# Schematic_Final.net
KiCad netlist of a schematic drawn in EAGLE
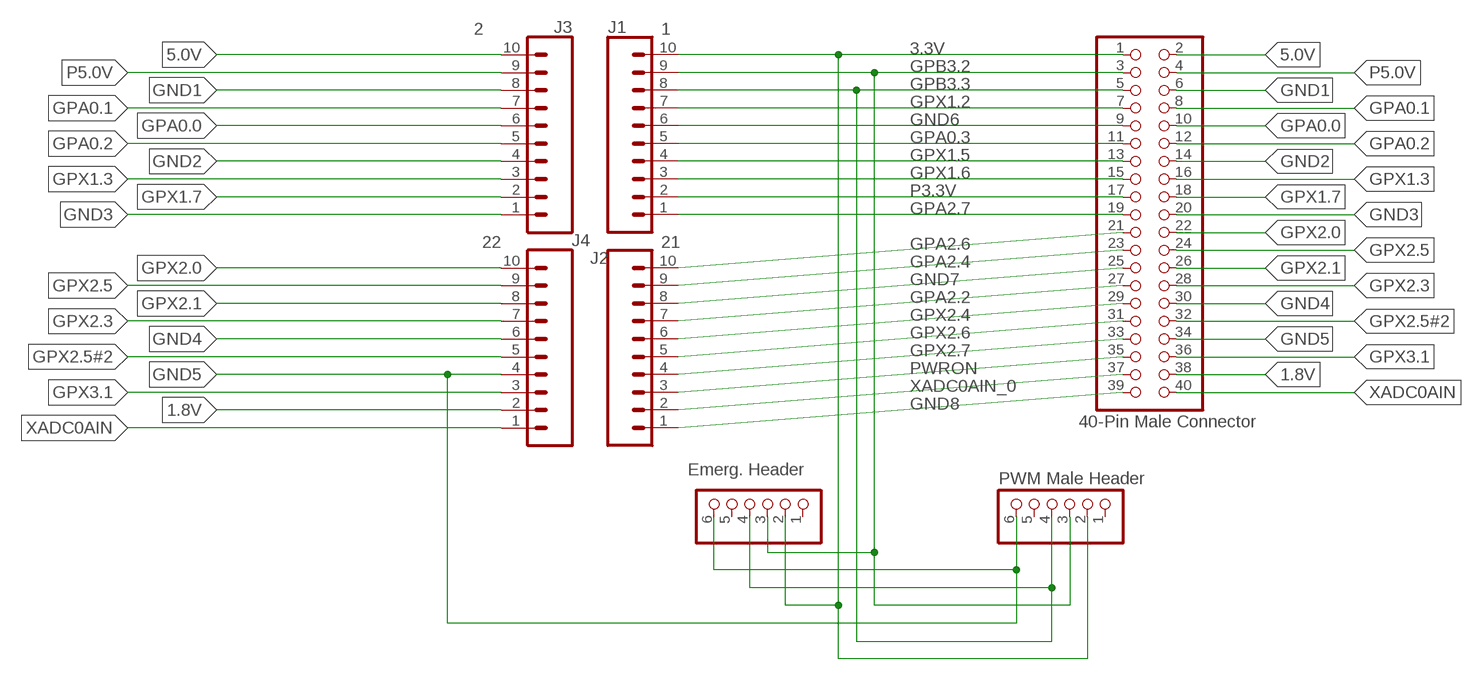
[diagram p0: schematic, sheet 1]

(export (version "E")
  (design (tool "Eeschema 10.0.6"))
  (components
    (comp (ref "J1")
      (value "1")
      (footprint "eagle-import:1X10")
      (libsource (lib "eagle-import") (part "CONN_10{dblquote}"))
    )
    (comp (ref "J2")
      (value "21")
      (footprint "eagle-import:1X10")
      (libsource (lib "eagle-import") (part "CONN_10{dblquote}"))
    )
    (comp (ref "J3")
      (value "2")
      (footprint "eagle-import:1X10")
      (libsource (lib "eagle-import") (part "CONN_10{dblquote}"))
    )
    (comp (ref "J4")
      (value "22")
      (footprint "eagle-import:1X10")
      (libsource (lib "eagle-import") (part "CONN_10{dblquote}"))
    )
    (comp (ref "JP1")
      (value "40-Pin Male Connector")
      (footprint "eagle-import:2X20")
      (libsource (lib "eagle-import") (part "PINHD-2X20"))
    )
    (comp (ref "JP2")
      (value "Emerg. Header")
      (footprint "eagle-import:1X06")
      (libsource (lib "eagle-import") (part "PINHD-1X6"))
    )
    (comp (ref "JP4")
      (value "PWM Male Header")
      (footprint "eagle-import:1X06")
      (libsource (lib "eagle-import") (part "PINHD-1X6"))
    )
  )
  (nets
    (net (code "1") (name "/3.3V") (class "Default")
      (node (ref "J1") (pin "10") (pinfunction "10_10") (pintype "passive"))
      (node (ref "JP1") (pin "1") (pinfunction "1_1") (pintype "passive"))
      (node (ref "JP2") (pin "2") (pinfunction "2_2") (pintype "passive"))
      (node (ref "JP4") (pin "2") (pinfunction "2_2") (pintype "passive"))
    )
    (net (code "2") (name "/GND6") (class "Default")
      (node (ref "J1") (pin "6") (pinfunction "6_6") (pintype "passive"))
      (node (ref "JP1") (pin "9") (pinfunction "9_9") (pintype "passive"))
    )
    (net (code "3") (name "/GND7") (class "Default")
      (node (ref "J2") (pin "8") (pinfunction "8_8") (pintype "passive"))
      (node (ref "JP1") (pin "25") (pinfunction "25_25") (pintype "passive"))
    )
    (net (code "4") (name "/GND8") (class "Default")
      (node (ref "J2") (pin "1") (pinfunction "1_1") (pintype "passive"))
      (node (ref "JP1") (pin "39") (pinfunction "39_39") (pintype "passive"))
    )
    (net (code "5") (name "/GPA0.3") (class "Default")
      (node (ref "J1") (pin "5") (pinfunction "5_5") (pintype "passive"))
      (node (ref "JP1") (pin "11") (pinfunction "11_11") (pintype "passive"))
    )
    (net (code "6") (name "/GPA2.2") (class "Default")
      (node (ref "J2") (pin "7") (pinfunction "7_7") (pintype "passive"))
      (node (ref "JP1") (pin "27") (pinfunction "27_27") (pintype "passive"))
    )
    (net (code "7") (name "/GPA2.4") (class "Default")
      (node (ref "J2") (pin "9") (pinfunction "9_9") (pintype "passive"))
      (node (ref "JP1") (pin "23") (pinfunction "23_23") (pintype "passive"))
    )
    (net (code "8") (name "/GPA2.6") (class "Default")
      (node (ref "J2") (pin "10") (pinfunction "10_10") (pintype "passive"))
      (node (ref "JP1") (pin "21") (pinfunction "21_21") (pintype "passive"))
    )
    (net (code "9") (name "/GPA2.7") (class "Default")
      (node (ref "J1") (pin "1") (pinfunction "1_1") (pintype "passive"))
      (node (ref "JP1") (pin "19") (pinfunction "19_19") (pintype "passive"))
    )
    (net (code "10") (name "/GPB3.2") (class "Default")
      (node (ref "J1") (pin "9") (pinfunction "9_9") (pintype "passive"))
      (node (ref "JP1") (pin "3") (pinfunction "3_3") (pintype "passive"))
      (node (ref "JP2") (pin "3") (pinfunction "3_3") (pintype "passive"))
      (node (ref "JP4") (pin "3") (pinfunction "3_3") (pintype "passive"))
    )
    (net (code "11") (name "/GPB3.3") (class "Default")
      (node (ref "J1") (pin "8") (pinfunction "8_8") (pintype "passive"))
      (node (ref "JP1") (pin "5") (pinfunction "5_5") (pintype "passive"))
      (node (ref "JP2") (pin "4") (pinfunction "4_4") (pintype "passive"))
      (node (ref "JP4") (pin "4") (pinfunction "4_4") (pintype "passive"))
    )
    (net (code "12") (name "/GPX1.2") (class "Default")
      (node (ref "J1") (pin "7") (pinfunction "7_7") (pintype "passive"))
      (node (ref "JP1") (pin "7") (pinfunction "7_7") (pintype "passive"))
    )
    (net (code "13") (name "/GPX1.5") (class "Default")
      (node (ref "J1") (pin "4") (pinfunction "4_4") (pintype "passive"))
      (node (ref "JP1") (pin "13") (pinfunction "13_13") (pintype "passive"))
    )
    (net (code "14") (name "/GPX1.6") (class "Default")
      (node (ref "J1") (pin "3") (pinfunction "3_3") (pintype "passive"))
      (node (ref "JP1") (pin "15") (pinfunction "15_15") (pintype "passive"))
    )
    (net (code "15") (name "/GPX2.4") (class "Default")
      (node (ref "J2") (pin "6") (pinfunction "6_6") (pintype "passive"))
      (node (ref "JP1") (pin "29") (pinfunction "29_29") (pintype "passive"))
    )
    (net (code "16") (name "/GPX2.6") (class "Default")
      (node (ref "J2") (pin "5") (pinfunction "5_5") (pintype "passive"))
      (node (ref "JP1") (pin "31") (pinfunction "31_31") (pintype "passive"))
    )
    (net (code "17") (name "/GPX2.7") (class "Default")
      (node (ref "J2") (pin "4") (pinfunction "4_4") (pintype "passive"))
      (node (ref "JP1") (pin "33") (pinfunction "33_33") (pintype "passive"))
    )
    (net (code "18") (name "/P3.3V") (class "Default")
      (node (ref "J1") (pin "2") (pinfunction "2_2") (pintype "passive"))
      (node (ref "JP1") (pin "17") (pinfunction "17_17") (pintype "passive"))
    )
    (net (code "19") (name "/PWRON") (class "Default")
      (node (ref "J2") (pin "3") (pinfunction "3_3") (pintype "passive"))
      (node (ref "JP1") (pin "35") (pinfunction "35_35") (pintype "passive"))
    )
    (net (code "20") (name "/XADC0AIN_0") (class "Default")
      (node (ref "J2") (pin "2") (pinfunction "2_2") (pintype "passive"))
      (node (ref "JP1") (pin "37") (pinfunction "37_37") (pintype "passive"))
    )
    (net (code "21") (name "1.8V") (class "Default")
      (node (ref "J4") (pin "2") (pinfunction "2_2") (pintype "passive"))
      (node (ref "JP1") (pin "38") (pinfunction "38_38") (pintype "passive"))
    )
    (net (code "22") (name "5.0V") (class "Default")
      (node (ref "J3") (pin "10") (pinfunction "10_10") (pintype "passive"))
      (node (ref "JP1") (pin "2") (pinfunction "2_2") (pintype "passive"))
    )
    (net (code "23") (name "GND1") (class "Default")
      (node (ref "J3") (pin "8") (pinfunction "8_8") (pintype "passive"))
      (node (ref "JP1") (pin "6") (pinfunction "6_6") (pintype "passive"))
    )
    (net (code "24") (name "GND2") (class "Default")
      (node (ref "J3") (pin "4") (pinfunction "4_4") (pintype "passive"))
      (node (ref "JP1") (pin "14") (pinfunction "14_14") (pintype "passive"))
    )
    (net (code "25") (name "GND3") (class "Default")
      (node (ref "J3") (pin "1") (pinfunction "1_1") (pintype "passive"))
      (node (ref "JP1") (pin "20") (pinfunction "20_20") (pintype "passive"))
    )
    (net (code "26") (name "GND4") (class "Default")
      (node (ref "J4") (pin "6") (pinfunction "6_6") (pintype "passive"))
      (node (ref "JP1") (pin "30") (pinfunction "30_30") (pintype "passive"))
    )
    (net (code "27") (name "GND5") (class "Default")
      (node (ref "J4") (pin "4") (pinfunction "4_4") (pintype "passive"))
      (node (ref "JP1") (pin "34") (pinfunction "34_34") (pintype "passive"))
      (node (ref "JP2") (pin "6") (pinfunction "6_6") (pintype "passive"))
      (node (ref "JP4") (pin "6") (pinfunction "6_6") (pintype "passive"))
    )
    (net (code "28") (name "GPA0.0") (class "Default")
      (node (ref "J3") (pin "6") (pinfunction "6_6") (pintype "passive"))
      (node (ref "JP1") (pin "10") (pinfunction "10_10") (pintype "passive"))
    )
    (net (code "29") (name "GPA0.1") (class "Default")
      (node (ref "J3") (pin "7") (pinfunction "7_7") (pintype "passive"))
      (node (ref "JP1") (pin "8") (pinfunction "8_8") (pintype "passive"))
    )
    (net (code "30") (name "GPA0.2") (class "Default")
      (node (ref "J3") (pin "5") (pinfunction "5_5") (pintype "passive"))
      (node (ref "JP1") (pin "12") (pinfunction "12_12") (pintype "passive"))
    )
    (net (code "31") (name "GPX1.3") (class "Default")
      (node (ref "J3") (pin "3") (pinfunction "3_3") (pintype "passive"))
      (node (ref "JP1") (pin "16") (pinfunction "16_16") (pintype "passive"))
    )
    (net (code "32") (name "GPX1.7") (class "Default")
      (node (ref "J3") (pin "2") (pinfunction "2_2") (pintype "passive"))
      (node (ref "JP1") (pin "18") (pinfunction "18_18") (pintype "passive"))
    )
    (net (code "33") (name "GPX2.0") (class "Default")
      (node (ref "J4") (pin "10") (pinfunction "10_10") (pintype "passive"))
      (node (ref "JP1") (pin "22") (pinfunction "22_22") (pintype "passive"))
    )
    (net (code "34") (name "GPX2.1") (class "Default")
      (node (ref "J4") (pin "8") (pinfunction "8_8") (pintype "passive"))
      (node (ref "JP1") (pin "26") (pinfunction "26_26") (pintype "passive"))
    )
    (net (code "35") (name "GPX2.3") (class "Default")
      (node (ref "J4") (pin "7") (pinfunction "7_7") (pintype "passive"))
      (node (ref "JP1") (pin "28") (pinfunction "28_28") (pintype "passive"))
    )
    (net (code "36") (name "GPX2.5") (class "Default")
      (node (ref "J4") (pin "9") (pinfunction "9_9") (pintype "passive"))
      (node (ref "JP1") (pin "24") (pinfunction "24_24") (pintype "passive"))
    )
    (net (code "37") (name "GPX2.5#2") (class "Default")
      (node (ref "J4") (pin "5") (pinfunction "5_5") (pintype "passive"))
      (node (ref "JP1") (pin "32") (pinfunction "32_32") (pintype "passive"))
    )
    (net (code "38") (name "GPX3.1") (class "Default")
      (node (ref "J4") (pin "3") (pinfunction "3_3") (pintype "passive"))
      (node (ref "JP1") (pin "36") (pinfunction "36_36") (pintype "passive"))
    )
    (net (code "39") (name "P5.0V") (class "Default")
      (node (ref "J3") (pin "9") (pinfunction "9_9") (pintype "passive"))
      (node (ref "JP1") (pin "4") (pinfunction "4_4") (pintype "passive"))
    )
    (net (code "40") (name "XADC0AIN") (class "Default")
      (node (ref "J4") (pin "1") (pinfunction "1_1") (pintype "passive"))
      (node (ref "JP1") (pin "40") (pinfunction "40_40") (pintype "passive"))
    )
    (net (code "41") (name "unconnected-(JP2-Pad1)") (class "Default")
      (node (ref "JP2") (pin "1") (pinfunction "1_1") (pintype "passive"))
    )
    (net (code "42") (name "unconnected-(JP2-Pad5)") (class "Default")
      (node (ref "JP2") (pin "5") (pinfunction "5_5") (pintype "passive"))
    )
    (net (code "43") (name "unconnected-(JP4-Pad1)") (class "Default")
      (node (ref "JP4") (pin "1") (pinfunction "1_1") (pintype "passive"))
    )
    (net (code "44") (name "unconnected-(JP4-Pad5)") (class "Default")
      (node (ref "JP4") (pin "5") (pinfunction "5_5") (pintype "passive"))
    )
  )
)
